# ctrlr.net
KiCad netlist of a schematic drawn in EAGLE
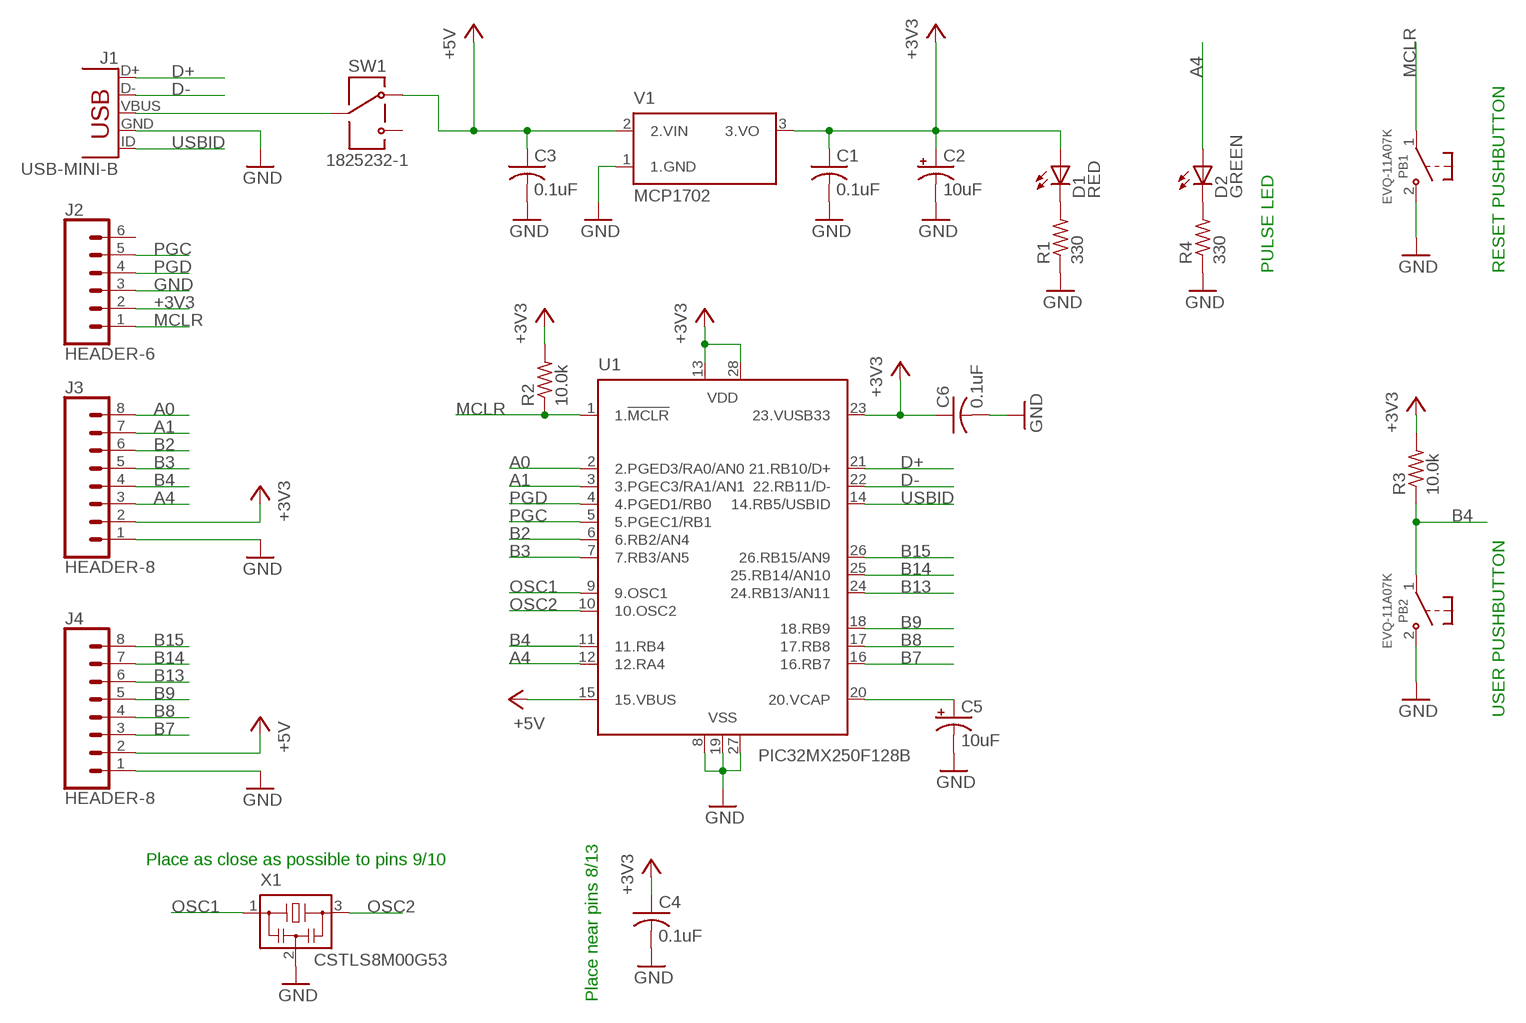
[diagram p0: schematic, sheet 1]

(export (version "E")
  (design (tool "Eeschema 10.0.6"))
  (components
    (comp (ref "C1")
      (value "0.1uF")
      (footprint "eagle-import:C1206")
      (libsource (lib "eagle-import") (part "C-USC1206"))
    )
    (comp (ref "C2")
      (value "10uF")
      (footprint "eagle-import:TAP5-50")
      (libsource (lib "eagle-import") (part "CPOL-USTAP5-50"))
    )
    (comp (ref "C3")
      (value "0.1uF")
      (footprint "eagle-import:C1206")
      (libsource (lib "eagle-import") (part "C-USC1206"))
    )
    (comp (ref "C4")
      (value "0.1uF")
      (footprint "eagle-import:C1206")
      (libsource (lib "eagle-import") (part "C-USC1206"))
    )
    (comp (ref "C5")
      (value "10uF")
      (footprint "eagle-import:TAP5-50")
      (libsource (lib "eagle-import") (part "CPOL-USTAP5-50"))
    )
    (comp (ref "C6")
      (value "0.1uF")
      (footprint "eagle-import:C1206")
      (libsource (lib "eagle-import") (part "C-USC1206"))
    )
    (comp (ref "D1")
      (value "LED-RED")
      (footprint "eagle-import:LED-3MM-V")
      (libsource (lib "eagle-import") (part "LED-RED"))
    )
    (comp (ref "D2")
      (value "LED-GREEN")
      (footprint "eagle-import:LED-3MM-V")
      (libsource (lib "eagle-import") (part "LED-GREEN"))
    )
    (comp (ref "J1")
      (value "USB-MINI-B")
      (footprint "eagle-import:USB-MB-TO")
      (libsource (lib "eagle-import") (part "USB-MINI-B"))
    )
    (comp (ref "J2")
      (value "HEADER-6")
      (footprint "eagle-import:CONN_1X06")
      (libsource (lib "eagle-import") (part "HEADER-6"))
    )
    (comp (ref "J3")
      (value "HEADER-8")
      (footprint "eagle-import:CONN_1X08")
      (libsource (lib "eagle-import") (part "HEADER-8"))
    )
    (comp (ref "J4")
      (value "HEADER-8")
      (footprint "eagle-import:CONN_1X08")
      (libsource (lib "eagle-import") (part "HEADER-8"))
    )
    (comp (ref "PB1")
      (value "EVQ-11A07K")
      (footprint "eagle-import:PCPIN-2")
      (libsource (lib "eagle-import") (part "EVQ-11A07K"))
    )
    (comp (ref "PB2")
      (value "EVQ-11A07K")
      (footprint "eagle-import:PCPIN-2")
      (libsource (lib "eagle-import") (part "EVQ-11A07K"))
    )
    (comp (ref "R1")
      (value "330")
      (footprint "eagle-import:R1206")
      (libsource (lib "eagle-import") (part "R-US_R1206"))
    )
    (comp (ref "R2")
      (value "10.0k")
      (footprint "eagle-import:R1206")
      (libsource (lib "eagle-import") (part "R-US_R1206"))
    )
    (comp (ref "R3")
      (value "10.0k")
      (footprint "eagle-import:R1206")
      (libsource (lib "eagle-import") (part "R-US_R1206"))
    )
    (comp (ref "R4")
      (value "330")
      (footprint "eagle-import:R1206")
      (libsource (lib "eagle-import") (part "R-US_R1206"))
    )
    (comp (ref "SW1")
      (value "1825232-1")
      (footprint "eagle-import:PCPIN-3SS")
      (libsource (lib "eagle-import") (part "1825232-1"))
    )
    (comp (ref "U1")
      (value "PIC32MX250F128B")
      (footprint "eagle-import:DIP28-3")
      (libsource (lib "eagle-import") (part "PIC32MX250F128B"))
    )
    (comp (ref "V1")
      (value "MCP1702")
      (footprint "eagle-import:TO-92")
      (libsource (lib "eagle-import") (part "MCP1702"))
    )
    (comp (ref "X1")
      (value "CSTLS8M00G53")
      (footprint "eagle-import:RAD-3-2.5")
      (libsource (lib "eagle-import") (part "CSTLS8M00G53"))
    )
  )
  (nets
    (net (code "1") (name "+3V3") (class "Default")
      (node (ref "C1") (pin "1") (pinfunction "1_1") (pintype "passive"))
      (node (ref "C2") (pin "+") (pinfunction "+_+") (pintype "passive"))
      (node (ref "C4") (pin "1") (pinfunction "1_1") (pintype "passive"))
      (node (ref "C6") (pin "1") (pinfunction "1_1") (pintype "passive"))
      (node (ref "D1") (pin "A") (pinfunction "A_A") (pintype "passive"))
      (node (ref "J2") (pin "2") (pinfunction "2._2") (pintype "passive"))
      (node (ref "J3") (pin "2") (pinfunction "2._2") (pintype "passive"))
      (node (ref "R2") (pin "2") (pinfunction "2_2") (pintype "passive"))
      (node (ref "R3") (pin "2") (pinfunction "2_2") (pintype "passive"))
      (node (ref "U1") (pin "13") (pinfunction "13.VDD_13") (pintype "power_in"))
      (node (ref "U1") (pin "23") (pinfunction "23.VUSB33_23") (pintype "bidirectional"))
      (node (ref "U1") (pin "28") (pinfunction "28.AVDD_28") (pintype "power_in"))
      (node (ref "V1") (pin "3") (pinfunction "3.VO_3") (pintype "output"))
    )
    (net (code "2") (name "+5V") (class "Default")
      (node (ref "C3") (pin "1") (pinfunction "1_1") (pintype "passive"))
      (node (ref "J4") (pin "2") (pinfunction "2._2") (pintype "passive"))
      (node (ref "SW1") (pin "1") (pinfunction "1_1") (pintype "bidirectional"))
      (node (ref "U1") (pin "15") (pinfunction "15.VBUS_15") (pintype "bidirectional"))
      (node (ref "V1") (pin "2") (pinfunction "2.VIN_2") (pintype "input"))
    )
    (net (code "3") (name "/A0") (class "Default")
      (node (ref "J3") (pin "8") (pinfunction "8._8") (pintype "passive"))
      (node (ref "U1") (pin "2") (pinfunction "2.PGED3/RA0/AN0_2") (pintype "bidirectional"))
    )
    (net (code "4") (name "/A1") (class "Default")
      (node (ref "J3") (pin "7") (pinfunction "7._7") (pintype "passive"))
      (node (ref "U1") (pin "3") (pinfunction "3.PGEC3/RA1/AN1_3") (pintype "bidirectional"))
    )
    (net (code "5") (name "/A4") (class "Default")
      (node (ref "D2") (pin "A") (pinfunction "A_A") (pintype "passive"))
      (node (ref "J3") (pin "3") (pinfunction "3._3") (pintype "passive"))
      (node (ref "U1") (pin "12") (pinfunction "12.RA4_12") (pintype "bidirectional"))
    )
    (net (code "6") (name "/B2") (class "Default")
      (node (ref "J3") (pin "6") (pinfunction "6._6") (pintype "passive"))
      (node (ref "U1") (pin "6") (pinfunction "6.RB2/AN4_6") (pintype "bidirectional"))
    )
    (net (code "7") (name "/B3") (class "Default")
      (node (ref "J3") (pin "5") (pinfunction "5._5") (pintype "passive"))
      (node (ref "U1") (pin "7") (pinfunction "7.RB3/AN5_7") (pintype "bidirectional"))
    )
    (net (code "8") (name "/B4") (class "Default")
      (node (ref "J3") (pin "4") (pinfunction "4._4") (pintype "passive"))
      (node (ref "PB2") (pin "1") (pinfunction "1.A_1") (pintype "bidirectional"))
      (node (ref "R3") (pin "1") (pinfunction "1_1") (pintype "passive"))
      (node (ref "U1") (pin "11") (pinfunction "11.RB4_11") (pintype "bidirectional"))
    )
    (net (code "9") (name "/B7") (class "Default")
      (node (ref "J4") (pin "3") (pinfunction "3._3") (pintype "passive"))
      (node (ref "U1") (pin "16") (pinfunction "16.RB7_16") (pintype "bidirectional"))
    )
    (net (code "10") (name "/B8") (class "Default")
      (node (ref "J4") (pin "4") (pinfunction "4._4") (pintype "passive"))
      (node (ref "U1") (pin "17") (pinfunction "17.RB8_17") (pintype "bidirectional"))
    )
    (net (code "11") (name "/B9") (class "Default")
      (node (ref "J4") (pin "5") (pinfunction "5._5") (pintype "passive"))
      (node (ref "U1") (pin "18") (pinfunction "18.RB9_18") (pintype "bidirectional"))
    )
    (net (code "12") (name "/B13") (class "Default")
      (node (ref "J4") (pin "6") (pinfunction "6._6") (pintype "passive"))
      (node (ref "U1") (pin "24") (pinfunction "24.RB13/AN11_24") (pintype "bidirectional"))
    )
    (net (code "13") (name "/B14") (class "Default")
      (node (ref "J4") (pin "7") (pinfunction "7._7") (pintype "passive"))
      (node (ref "U1") (pin "25") (pinfunction "25.RB14/AN10_25") (pintype "bidirectional"))
    )
    (net (code "14") (name "/B15") (class "Default")
      (node (ref "J4") (pin "8") (pinfunction "8._8") (pintype "passive"))
      (node (ref "U1") (pin "26") (pinfunction "26.RB15/AN9_26") (pintype "bidirectional"))
    )
    (net (code "15") (name "/D+") (class "Default")
      (node (ref "J1") (pin "D+") (pinfunction "D+_D+") (pintype "bidirectional"))
      (node (ref "U1") (pin "21") (pinfunction "21.RB10/D+_21") (pintype "bidirectional"))
    )
    (net (code "16") (name "/D-") (class "Default")
      (node (ref "J1") (pin "D-") (pinfunction "D-_D-") (pintype "bidirectional"))
      (node (ref "U1") (pin "22") (pinfunction "22.RB11/D-_22") (pintype "bidirectional"))
    )
    (net (code "17") (name "/MCLR") (class "Default")
      (node (ref "J2") (pin "1") (pinfunction "1._1") (pintype "passive"))
      (node (ref "PB1") (pin "1") (pinfunction "1.A_1") (pintype "bidirectional"))
      (node (ref "R2") (pin "1") (pinfunction "1_1") (pintype "passive"))
      (node (ref "U1") (pin "1") (pinfunction "1.~{MCLR}_1") (pintype "input"))
    )
    (net (code "18") (name "/OSC1") (class "Default")
      (node (ref "U1") (pin "9") (pinfunction "9.OSC1_9") (pintype "input"))
      (node (ref "X1") (pin "1") (pinfunction "1_1") (pintype "passive"))
    )
    (net (code "19") (name "/OSC2") (class "Default")
      (node (ref "U1") (pin "10") (pinfunction "10.OSC2_10") (pintype "output"))
      (node (ref "X1") (pin "3") (pinfunction "3_3") (pintype "passive"))
    )
    (net (code "20") (name "/PGC") (class "Default")
      (node (ref "J2") (pin "5") (pinfunction "5._5") (pintype "passive"))
      (node (ref "U1") (pin "5") (pinfunction "5.PGEC1/RB1_5") (pintype "bidirectional"))
    )
    (net (code "21") (name "/PGD") (class "Default")
      (node (ref "J2") (pin "4") (pinfunction "4._4") (pintype "passive"))
      (node (ref "U1") (pin "4") (pinfunction "4.PGED1/RB0_4") (pintype "bidirectional"))
    )
    (net (code "22") (name "/USBID") (class "Default")
      (node (ref "J1") (pin "ID") (pinfunction "ID_ID") (pintype "bidirectional"))
      (node (ref "U1") (pin "14") (pinfunction "14.RB5/USBID_14") (pintype "bidirectional"))
    )
    (net (code "23") (name "GND") (class "Default")
      (node (ref "C1") (pin "2") (pinfunction "2_2") (pintype "passive"))
      (node (ref "C2") (pin "-") (pinfunction "-_-") (pintype "passive"))
      (node (ref "C3") (pin "2") (pinfunction "2_2") (pintype "passive"))
      (node (ref "C4") (pin "2") (pinfunction "2_2") (pintype "passive"))
      (node (ref "C5") (pin "-") (pinfunction "-_-") (pintype "passive"))
      (node (ref "C6") (pin "2") (pinfunction "2_2") (pintype "passive"))
      (node (ref "J1") (pin "GND") (pinfunction "GND_GND") (pintype "bidirectional"))
      (node (ref "J2") (pin "3") (pinfunction "3._3") (pintype "passive"))
      (node (ref "J3") (pin "1") (pinfunction "1._1") (pintype "passive"))
      (node (ref "J4") (pin "1") (pinfunction "1._1") (pintype "passive"))
      (node (ref "PB1") (pin "2") (pinfunction "2.B_2") (pintype "bidirectional"))
      (node (ref "PB2") (pin "2") (pinfunction "2.B_2") (pintype "bidirectional"))
      (node (ref "R1") (pin "1") (pinfunction "1_1") (pintype "passive"))
      (node (ref "R4") (pin "1") (pinfunction "1_1") (pintype "passive"))
      (node (ref "U1") (pin "19") (pinfunction "19.VSS_19") (pintype "power_in"))
      (node (ref "U1") (pin "27") (pinfunction "27.AVSS_27") (pintype "bidirectional"))
      (node (ref "U1") (pin "8") (pinfunction "8.VSS_8") (pintype "power_in"))
      (node (ref "V1") (pin "1") (pinfunction "1.GND_1") (pintype "passive"))
      (node (ref "X1") (pin "2") (pinfunction "2_2") (pintype "passive"))
    )
    (net (code "24") (name "Net-(D1-C)") (class "Default")
      (node (ref "D1") (pin "K") (pinfunction "C_K") (pintype "passive"))
      (node (ref "R1") (pin "2") (pinfunction "2_2") (pintype "passive"))
    )
    (net (code "25") (name "Net-(D2-C)") (class "Default")
      (node (ref "D2") (pin "K") (pinfunction "C_K") (pintype "passive"))
      (node (ref "R4") (pin "2") (pinfunction "2_2") (pintype "passive"))
    )
    (net (code "26") (name "Net-(J1-PadVBUS)") (class "Default")
      (node (ref "J1") (pin "VBUS") (pinfunction "VBUS_VBUS") (pintype "bidirectional"))
      (node (ref "SW1") (pin "2") (pinfunction "2_2") (pintype "bidirectional"))
    )
    (net (code "27") (name "Net-(U1-20.VCAP)") (class "Default")
      (node (ref "C5") (pin "+") (pinfunction "+_+") (pintype "passive"))
      (node (ref "U1") (pin "20") (pinfunction "20.VCAP_20") (pintype "bidirectional"))
    )
    (net (code "28") (name "unconnected-(J2-6.-Pad6)") (class "Default")
      (node (ref "J2") (pin "6") (pinfunction "6._6") (pintype "passive"))
    )
    (net (code "29") (name "unconnected-(SW1-Pad3)") (class "Default")
      (node (ref "SW1") (pin "3") (pinfunction "3_3") (pintype "bidirectional"))
    )
  )
)
